# PWM_Haptics_Address_Selector.net
KiCad netlist of a schematic drawn in EasyEDA Pro
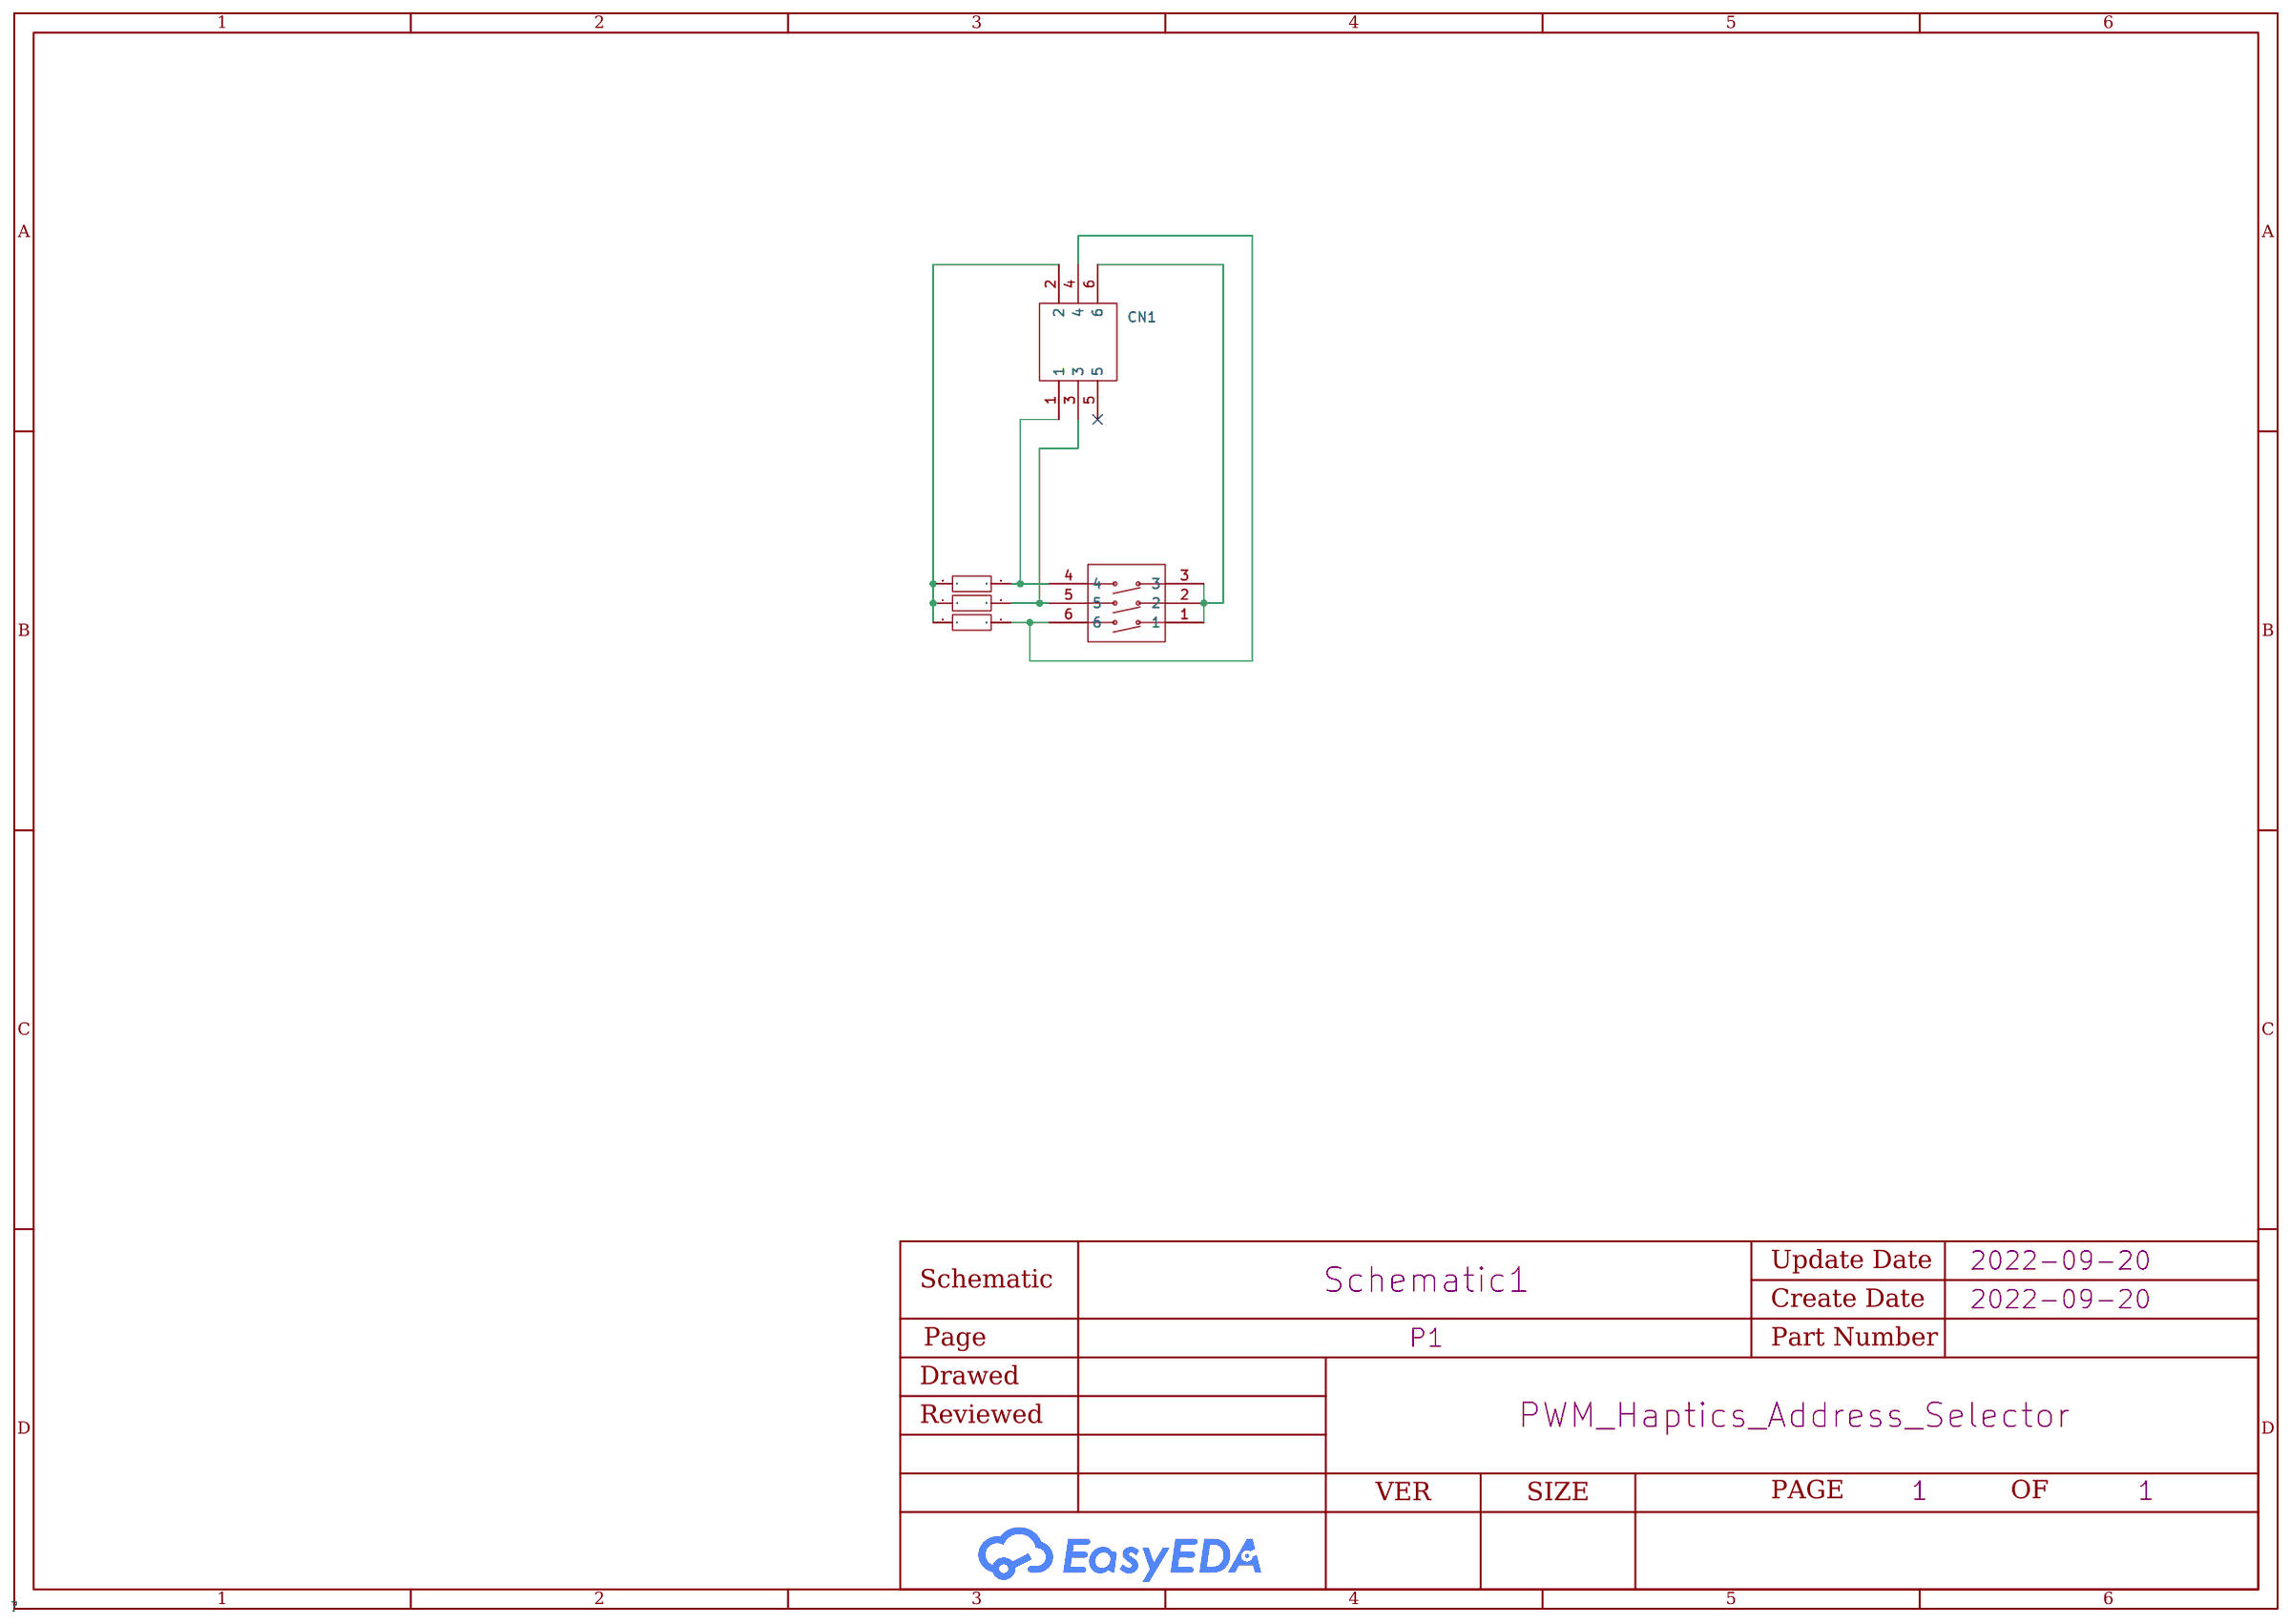
[diagram p0: schematic sheet]

(export (version "E")
  (design (tool "Eeschema 10.0.6"))
  (components
    (comp (ref "CN1")
      (value "~")
      (footprint "easyedapro:CONN-TH_FC-2X3P-2.54MM")
      (description "连接器类型:IDC连接器;间距:2.54mm;每排PIN数:3;排数:2;行距:2.54mm;封装形式:三件式(连接器+压排+反折盖);触头材质:黄铜;触头镀层:金;")
      (fields (field (name "Manufacturer Part") "2.54-2*3P压线头") (field (name "Manufacturer") "BOOMELE(博穆精密)"))
      (libsource (lib "easyedapro") (part "2.54mm2*3PCrimping terminals"))
    )
    (comp (ref "R1")
      (value "1kΩ")
      (footprint "easyedapro:R0603")
      (description "电阻类型:厚膜电阻;阻值:1kΩ;精度:±1%;功率:1/10W;温度系数:±100ppm/;最大工作电压:75V;工作温度范围:-55~+155;")
      (fields
        (field (name "Manufacturer Part") "0603WAF1001T5E")
        (field (name "Manufacturer") "UNI-ROYAL(厚声)")
      )
      (libsource (lib "easyedapro") (part "0603WAF1001T5E"))
    )
    (comp (ref "R2")
      (value "1kΩ")
      (footprint "easyedapro:R0603")
      (description "电阻类型:厚膜电阻;阻值:1kΩ;精度:±1%;功率:1/10W;温度系数:±100ppm/;最大工作电压:75V;工作温度范围:-55~+155;")
      (fields
        (field (name "Manufacturer Part") "0603WAF1001T5E")
        (field (name "Manufacturer") "UNI-ROYAL(厚声)")
      )
      (libsource (lib "easyedapro") (part "0603WAF1001T5E"))
    )
    (comp (ref "R3")
      (value "1kΩ")
      (footprint "easyedapro:R0603")
      (description "电阻类型:厚膜电阻;阻值:1kΩ;精度:±1%;功率:1/10W;温度系数:±100ppm/;最大工作电压:75V;工作温度范围:-55~+155;")
      (fields
        (field (name "Manufacturer Part") "0603WAF1001T5E")
        (field (name "Manufacturer") "UNI-ROYAL(厚声)")
      )
      (libsource (lib "easyedapro") (part "0603WAF1001T5E"))
    )
    (comp (ref "SW1")
      (value "EM-03KP")
      (footprint "easyedapro:SW-SMD_EM-03KP")
      (fields (field (name "Manufacturer") "HRO"))
      (libsource (lib "easyedapro") (part "EM-03KP"))
    )
  )
  (nets
    (net (code "1") (name "Net-(CN1-Pad1)") (class "Default")
      (node (ref "CN1") (pin "1") (pinfunction "1_1") (pintype "input"))
      (node (ref "R2") (pin "1") (pinfunction "1_1") (pintype "input"))
      (node (ref "SW1") (pin "4") (pinfunction "4_4") (pintype "input"))
    )
    (net (code "2") (name "Net-(CN1-Pad2)") (class "Default")
      (node (ref "CN1") (pin "2") (pinfunction "2_2") (pintype "input"))
      (node (ref "R1") (pin "2") (pinfunction "2_2") (pintype "input"))
      (node (ref "R2") (pin "2") (pinfunction "2_2") (pintype "input"))
      (node (ref "R3") (pin "1") (pinfunction "1_1") (pintype "input"))
    )
    (net (code "3") (name "Net-(CN1-Pad3)") (class "Default")
      (node (ref "CN1") (pin "3") (pinfunction "3_3") (pintype "input"))
      (node (ref "R3") (pin "2") (pinfunction "2_2") (pintype "input"))
      (node (ref "SW1") (pin "5") (pinfunction "5_5") (pintype "input"))
    )
    (net (code "4") (name "Net-(CN1-Pad4)") (class "Default")
      (node (ref "CN1") (pin "4") (pinfunction "4_4") (pintype "input"))
      (node (ref "R1") (pin "1") (pinfunction "1_1") (pintype "input"))
      (node (ref "SW1") (pin "6") (pinfunction "6_6") (pintype "input"))
    )
    (net (code "5") (name "Net-(CN1-Pad6)") (class "Default")
      (node (ref "CN1") (pin "6") (pinfunction "6_6") (pintype "input"))
      (node (ref "SW1") (pin "1") (pinfunction "1_1") (pintype "input"))
      (node (ref "SW1") (pin "2") (pinfunction "2_2") (pintype "input"))
      (node (ref "SW1") (pin "3") (pinfunction "3_3") (pintype "input"))
    )
    (net (code "6") (name "unconnected-(CN1-Pad5)") (class "Default")
      (node (ref "CN1") (pin "5") (pinfunction "5_5") (pintype "input+no_connect"))
    )
  )
)
